# dekatron-sim-4017-a4.net
KiCad netlist of a schematic drawn in EAGLE
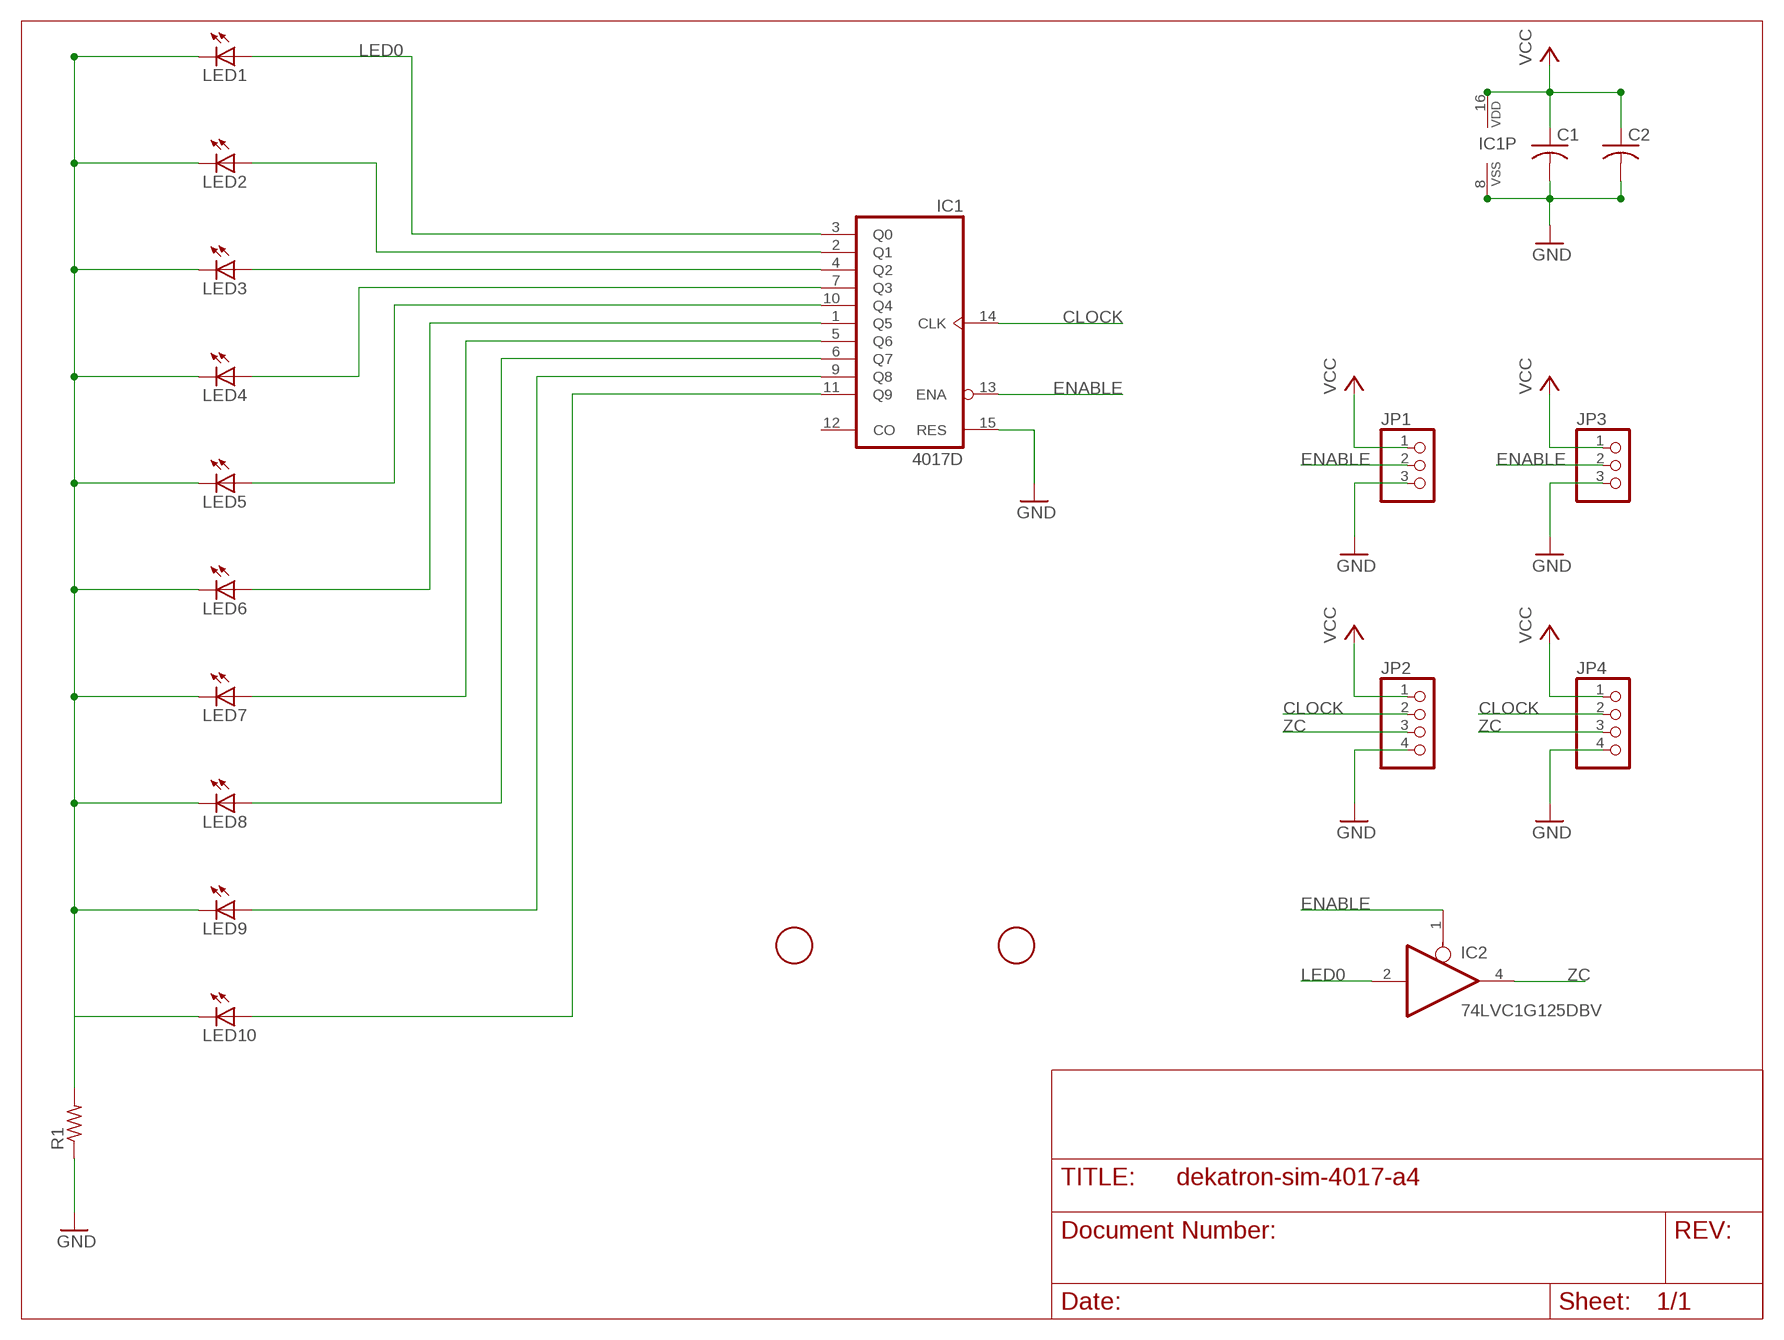
[diagram p0: schematic, sheet 1]

(export (version "E")
  (design (tool "Eeschema 10.0.6"))
  (components
    (comp (ref "C1")
      (value "C-USC0805")
      (footprint "eagle-import:C0805")
      (libsource (lib "eagle-import") (part "C-USC0805"))
    )
    (comp (ref "C2")
      (value "C-USC0805")
      (footprint "eagle-import:C0805")
      (libsource (lib "eagle-import") (part "C-USC0805"))
    )
    (comp (ref "FID1")
      (value "FIDUCIAL")
      (footprint "eagle-import:FIDUCIAL_1MM")
      (libsource (lib "eagle-import") (part "FIDUCIAL"))
    )
    (comp (ref "FID2")
      (value "FIDUCIAL")
      (footprint "eagle-import:FIDUCIAL_1MM")
      (libsource (lib "eagle-import") (part "FIDUCIAL"))
    )
    (comp (ref "IC1")
      (value "4017D")
      (footprint "eagle-import:SO16")
      (libsource (lib "eagle-import") (part "4017D"))
    )
    (comp (ref "IC2")
      (value "74LVC1G125DBV")
      (footprint "eagle-import:SOT23-5")
      (libsource (lib "eagle-import") (part "741G125DBVLVC"))
    )
    (comp (ref "JP1")
      (value "PINHD-1X3")
      (footprint "eagle-import:1X03")
      (libsource (lib "eagle-import") (part "PINHD-1X3"))
    )
    (comp (ref "JP2")
      (value "PINHD-1X4")
      (footprint "eagle-import:1X04")
      (libsource (lib "eagle-import") (part "PINHD-1X4"))
    )
    (comp (ref "JP3")
      (value "PINHD-1X3")
      (footprint "eagle-import:1X03")
      (libsource (lib "eagle-import") (part "PINHD-1X3"))
    )
    (comp (ref "JP4")
      (value "PINHD-1X4")
      (footprint "eagle-import:1X04")
      (libsource (lib "eagle-import") (part "PINHD-1X4"))
    )
    (comp (ref "LED1")
      (value "RED")
      (footprint "eagle-import:CHIP-LED0805")
      (libsource (lib "eagle-import") (part "LEDCHIP-LED0805"))
    )
    (comp (ref "LED2")
      (value "RED")
      (footprint "eagle-import:CHIP-LED0805")
      (libsource (lib "eagle-import") (part "LEDCHIP-LED0805"))
    )
    (comp (ref "LED3")
      (value "RED")
      (footprint "eagle-import:CHIP-LED0805")
      (libsource (lib "eagle-import") (part "LEDCHIP-LED0805"))
    )
    (comp (ref "LED4")
      (value "RED")
      (footprint "eagle-import:CHIP-LED0805")
      (libsource (lib "eagle-import") (part "LEDCHIP-LED0805"))
    )
    (comp (ref "LED5")
      (value "RED")
      (footprint "eagle-import:CHIP-LED0805")
      (libsource (lib "eagle-import") (part "LEDCHIP-LED0805"))
    )
    (comp (ref "LED6")
      (value "RED")
      (footprint "eagle-import:CHIP-LED0805")
      (libsource (lib "eagle-import") (part "LEDCHIP-LED0805"))
    )
    (comp (ref "LED7")
      (value "RED")
      (footprint "eagle-import:CHIP-LED0805")
      (libsource (lib "eagle-import") (part "LEDCHIP-LED0805"))
    )
    (comp (ref "LED8")
      (value "RED")
      (footprint "eagle-import:CHIP-LED0805")
      (libsource (lib "eagle-import") (part "LEDCHIP-LED0805"))
    )
    (comp (ref "LED9")
      (value "RED")
      (footprint "eagle-import:CHIP-LED0805")
      (libsource (lib "eagle-import") (part "LEDCHIP-LED0805"))
    )
    (comp (ref "LED10")
      (value "RED")
      (footprint "eagle-import:CHIP-LED0805")
      (libsource (lib "eagle-import") (part "LEDCHIP-LED0805"))
    )
    (comp (ref "R1")
      (value "R-US_R0805")
      (footprint "eagle-import:R0805")
      (libsource (lib "eagle-import") (part "R-US_R0805"))
    )
  )
  (nets
    (net (code "1") (name "/CLOCK") (class "Default")
      (node (ref "IC1") (pin "14") (pinfunction "CLK_14") (pintype "input"))
      (node (ref "JP2") (pin "2") (pinfunction "2_2") (pintype "passive"))
      (node (ref "JP4") (pin "2") (pinfunction "2_2") (pintype "passive"))
    )
    (net (code "2") (name "/ENABLE") (class "Default")
      (node (ref "IC1") (pin "13") (pinfunction "ENA_13") (pintype "input"))
      (node (ref "IC2") (pin "1") (pinfunction "OE_1") (pintype "input"))
      (node (ref "JP1") (pin "2") (pinfunction "2_2") (pintype "passive"))
      (node (ref "JP3") (pin "2") (pinfunction "2_2") (pintype "passive"))
    )
    (net (code "3") (name "/LED0") (class "Default")
      (node (ref "IC1") (pin "3") (pinfunction "Q0_3") (pintype "output"))
      (node (ref "IC2") (pin "2") (pinfunction "I_2") (pintype "input"))
      (node (ref "LED1") (pin "A") (pinfunction "A_A") (pintype "passive"))
    )
    (net (code "4") (name "/ZC") (class "Default")
      (node (ref "IC2") (pin "4") (pinfunction "O_4") (pintype "tri_state"))
      (node (ref "JP2") (pin "3") (pinfunction "3_3") (pintype "passive"))
      (node (ref "JP4") (pin "3") (pinfunction "3_3") (pintype "passive"))
    )
    (net (code "5") (name "GND") (class "Default")
      (node (ref "C1") (pin "2") (pinfunction "2_2") (pintype "passive"))
      (node (ref "C2") (pin "2") (pinfunction "2_2") (pintype "passive"))
      (node (ref "IC1") (pin "15") (pinfunction "RES_15") (pintype "input"))
      (node (ref "IC1") (pin "8") (pinfunction "VSS_8") (pintype "power_in"))
      (node (ref "JP1") (pin "3") (pinfunction "3_3") (pintype "passive"))
      (node (ref "JP2") (pin "4") (pinfunction "4_4") (pintype "passive"))
      (node (ref "JP3") (pin "3") (pinfunction "3_3") (pintype "passive"))
      (node (ref "JP4") (pin "4") (pinfunction "4_4") (pintype "passive"))
      (node (ref "R1") (pin "1") (pinfunction "1_1") (pintype "passive"))
    )
    (net (code "6") (name "Net-(IC1A-Q1)") (class "Default")
      (node (ref "IC1") (pin "2") (pinfunction "Q1_2") (pintype "output"))
      (node (ref "LED2") (pin "A") (pinfunction "A_A") (pintype "passive"))
    )
    (net (code "7") (name "Net-(IC1A-Q2)") (class "Default")
      (node (ref "IC1") (pin "4") (pinfunction "Q2_4") (pintype "output"))
      (node (ref "LED3") (pin "A") (pinfunction "A_A") (pintype "passive"))
    )
    (net (code "8") (name "Net-(IC1A-Q3)") (class "Default")
      (node (ref "IC1") (pin "7") (pinfunction "Q3_7") (pintype "output"))
      (node (ref "LED4") (pin "A") (pinfunction "A_A") (pintype "passive"))
    )
    (net (code "9") (name "Net-(IC1A-Q4)") (class "Default")
      (node (ref "IC1") (pin "10") (pinfunction "Q4_10") (pintype "output"))
      (node (ref "LED5") (pin "A") (pinfunction "A_A") (pintype "passive"))
    )
    (net (code "10") (name "Net-(IC1A-Q5)") (class "Default")
      (node (ref "IC1") (pin "1") (pinfunction "Q5_1") (pintype "output"))
      (node (ref "LED6") (pin "A") (pinfunction "A_A") (pintype "passive"))
    )
    (net (code "11") (name "Net-(IC1A-Q6)") (class "Default")
      (node (ref "IC1") (pin "5") (pinfunction "Q6_5") (pintype "output"))
      (node (ref "LED7") (pin "A") (pinfunction "A_A") (pintype "passive"))
    )
    (net (code "12") (name "Net-(IC1A-Q7)") (class "Default")
      (node (ref "IC1") (pin "6") (pinfunction "Q7_6") (pintype "output"))
      (node (ref "LED8") (pin "A") (pinfunction "A_A") (pintype "passive"))
    )
    (net (code "13") (name "Net-(IC1A-Q8)") (class "Default")
      (node (ref "IC1") (pin "9") (pinfunction "Q8_9") (pintype "output"))
      (node (ref "LED9") (pin "A") (pinfunction "A_A") (pintype "passive"))
    )
    (net (code "14") (name "Net-(IC1A-Q9)") (class "Default")
      (node (ref "IC1") (pin "11") (pinfunction "Q9_11") (pintype "output"))
      (node (ref "LED10") (pin "A") (pinfunction "A_A") (pintype "passive"))
    )
    (net (code "15") (name "Net-(LED1-PadC)") (class "Default")
      (node (ref "LED1") (pin "C") (pinfunction "C_C") (pintype "passive"))
      (node (ref "LED10") (pin "C") (pinfunction "C_C") (pintype "passive"))
      (node (ref "LED2") (pin "C") (pinfunction "C_C") (pintype "passive"))
      (node (ref "LED3") (pin "C") (pinfunction "C_C") (pintype "passive"))
      (node (ref "LED4") (pin "C") (pinfunction "C_C") (pintype "passive"))
      (node (ref "LED5") (pin "C") (pinfunction "C_C") (pintype "passive"))
      (node (ref "LED6") (pin "C") (pinfunction "C_C") (pintype "passive"))
      (node (ref "LED7") (pin "C") (pinfunction "C_C") (pintype "passive"))
      (node (ref "LED8") (pin "C") (pinfunction "C_C") (pintype "passive"))
      (node (ref "LED9") (pin "C") (pinfunction "C_C") (pintype "passive"))
      (node (ref "R1") (pin "2") (pinfunction "2_2") (pintype "passive"))
    )
    (net (code "16") (name "VCC") (class "Default")
      (node (ref "C1") (pin "1") (pinfunction "1_1") (pintype "passive"))
      (node (ref "C2") (pin "1") (pinfunction "1_1") (pintype "passive"))
      (node (ref "IC1") (pin "16") (pinfunction "VDD_16") (pintype "power_in"))
      (node (ref "JP1") (pin "1") (pinfunction "1_1") (pintype "passive"))
      (node (ref "JP2") (pin "1") (pinfunction "1_1") (pintype "passive"))
      (node (ref "JP3") (pin "1") (pinfunction "1_1") (pintype "passive"))
      (node (ref "JP4") (pin "1") (pinfunction "1_1") (pintype "passive"))
    )
    (net (code "17") (name "unconnected-(IC1A-CO-Pad12)") (class "Default")
      (node (ref "IC1") (pin "12") (pinfunction "CO_12") (pintype "output"))
    )
  )
)
